# BOOST.net
KiCad netlist of a schematic drawn in Altium Designer
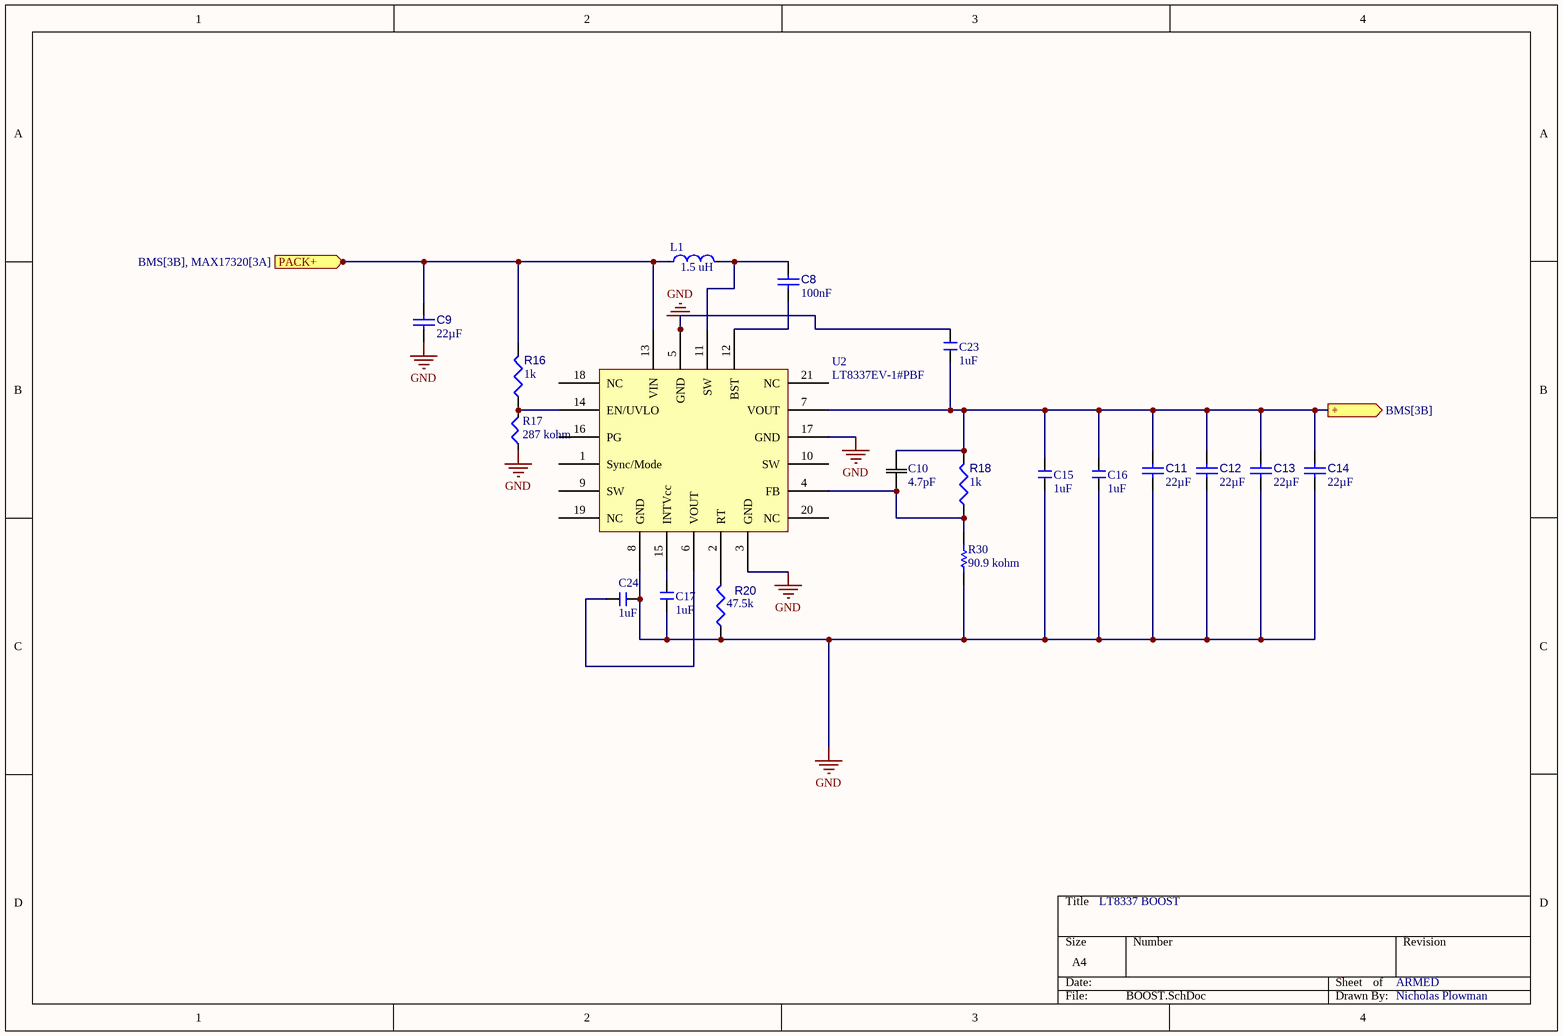
[diagram p0: BOOST.SchDoc]

(export (version "E")
  (design (tool "Eeschema 10.0.6"))
  (components
    (comp (ref "C8")
      (value "100nF")
      (footprint "CAPC1005X56X25LL10T15")
      (description "Chip Capacitor, 0.1 uF, +/- 5%, 16 V, 0402 (1005 Metric)")
      (fields (field (name "TOLERANCE") "5%") (field (name "Comment") "Capacitor 0.1 uF +/- 5% 16 V 0402"))
      (libsource (lib "Americas- Augmented Reality for Medicine- University of Calgary") (part "CAP-NP-2"))
    )
    (comp (ref "C9")
      (value "22µF")
      (footprint "CAPC0805(2012)145_L")
      (description "Chip Capacitor, 22µF +/-40%, 16V, 0805, Thickness 1.45 mm")
      (fields (field (name "TOLERANCE") "5%") (field (name "Comment") "Capacitor 22µF +/-40% 16V 0805"))
      (libsource (lib "Americas- Augmented Reality for Medicine- University of Calgary") (part "CAP-NP-2"))
    )
    (comp (ref "C10")
      (value "600L4R7BT200T4K")
      (footprint "600L4R7BT200T4K-Footprint-1")
      (description "Cap Cer 4.7PF 200V C0G/NP0 0402")
      (fields (field (name "PARAMETER 1") "4.7pF"))
      (libsource (lib "Americas- Augmented Reality for Medicine- University of Calgary") (part "600L4R7BT200T4K-Symbol-1"))
    )
    (comp (ref "C11")
      (value "22µF")
      (footprint "CAPC0805(2012)145_L")
      (description "Chip Capacitor, 22µF +/-40%, 16V, 0805, Thickness 1.45 mm")
      (fields (field (name "TOLERANCE") "5%") (field (name "Comment") "Capacitor 22µF +/-40% 16V 0805"))
      (libsource (lib "Americas- Augmented Reality for Medicine- University of Calgary") (part "CAP-NP-2"))
    )
    (comp (ref "C12")
      (value "22µF")
      (footprint "CAPC0805(2012)145_L")
      (description "Chip Capacitor, 22µF +/-40%, 16V, 0805, Thickness 1.45 mm")
      (fields (field (name "TOLERANCE") "5%") (field (name "Comment") "Capacitor 22µF +/-40% 16V 0805"))
      (libsource (lib "Americas- Augmented Reality for Medicine- University of Calgary") (part "CAP-NP-2"))
    )
    (comp (ref "C13")
      (value "22µF")
      (footprint "CAPC0805(2012)145_L")
      (description "Chip Capacitor, 22µF +/-40%, 16V, 0805, Thickness 1.45 mm")
      (fields (field (name "TOLERANCE") "5%") (field (name "Comment") "Capacitor 22µF +/-40% 16V 0805"))
      (libsource (lib "Americas- Augmented Reality for Medicine- University of Calgary") (part "CAP-NP-2"))
    )
    (comp (ref "C14")
      (value "22µF")
      (footprint "CAPC0805(2012)145_L")
      (description "Chip Capacitor, 22µF +/-40%, 16V, 0805, Thickness 1.45 mm")
      (fields (field (name "TOLERANCE") "5%") (field (name "Comment") "Capacitor 22µF +/-40% 16V 0805"))
      (libsource (lib "Americas- Augmented Reality for Medicine- University of Calgary") (part "CAP-NP-2"))
    )
    (comp (ref "C15")
      (value "25V 1uF 0603 CAP")
      (footprint "25V 1uF 0603 CAP-Footprint-1")
      (description "0603 1 uF 25 V ±10 % Tolerance X5R SMT Multilayer Ceramic Capacitor")
      (fields (field (name "PARAMETER 1") "1uF"))
      (libsource (lib "Americas- Augmented Reality for Medicine- University of Calgary") (part "1uF"))
    )
    (comp (ref "C16")
      (value "25V 1uF 0603 CAP")
      (footprint "25V 1uF 0603 CAP-Footprint-1")
      (description "0603 1 uF 25 V ±10 % Tolerance X5R SMT Multilayer Ceramic Capacitor")
      (fields (field (name "PARAMETER 1") "1uF"))
      (libsource (lib "Americas- Augmented Reality for Medicine- University of Calgary") (part "1uF"))
    )
    (comp (ref "C17")
      (value "25V 1uF 0603 CAP")
      (footprint "25V 1uF 0603 CAP-Footprint-1")
      (description "0603 1 uF 25 V ±10 % Tolerance X5R SMT Multilayer Ceramic Capacitor")
      (fields (field (name "PARAMETER 1") "1uF"))
      (libsource (lib "Americas- Augmented Reality for Medicine- University of Calgary") (part "1uF"))
    )
    (comp (ref "C23")
      (value "25V 1uF 0603 CAP")
      (footprint "25V 1uF 0603 CAP-Footprint-1")
      (description "0603 1 uF 25 V ±10 % Tolerance X5R SMT Multilayer Ceramic Capacitor")
      (fields (field (name "PARAMETER 1") "1uF"))
      (libsource (lib "Americas- Augmented Reality for Medicine- University of Calgary") (part "1uF"))
    )
    (comp (ref "C24")
      (value "25V 1uF 0603 CAP")
      (footprint "25V 1uF 0603 CAP-Footprint-1")
      (description "0603 1 uF 25 V ±10 % Tolerance X5R SMT Multilayer Ceramic Capacitor")
      (fields (field (name "PARAMETER 1") "1uF"))
      (libsource (lib "Americas- Augmented Reality for Medicine- University of Calgary") (part "1uF"))
    )
    (comp (ref "L1")
      (value "1.5 uH")
      (footprint "FP-LB3225-2_5-0_2-IPC_A")
      (fields (field (name "Comment") "LBC3225T1R5MR"))
      (libsource (lib "Americas- Augmented Reality for Medicine- University of Calgary") (part "725321dda6339637d4d059423bc1c3c"))
    )
    (comp (ref "R16")
      (value "1k")
      (footprint "RESC0805(2012)_L")
      (description "1K 0.125W 5% 0805 (2012 Metric)  SMD")
      (fields (field (name "TOLERANCE") "5%") (field (name "POWER") "125mW"))
      (libsource (lib "Americas- Augmented Reality for Medicine- University of Calgary") (part "1KR5J"))
    )
    (comp (ref "R17")
      (value "RMCF0603FT287K")
      (footprint "RMCF0603FT287K-Footprint-1")
      (description "Res Thick Film 0603 287K Ohm 1% 1/10W ±100ppm/°C Molded SMD SMD Paper T/R")
      (fields (field (name "PARAMETER 1") "287 kohm"))
      (libsource (lib "Americas- Augmented Reality for Medicine- University of Calgary") (part "287KOhm Resistor 0603"))
    )
    (comp (ref "R18")
      (value "1k")
      (footprint "RESC0805(2012)_L")
      (description "1K 0.125W 5% 0805 (2012 Metric)  SMD")
      (fields (field (name "TOLERANCE") "5%") (field (name "POWER") "125mW"))
      (libsource (lib "Americas- Augmented Reality for Medicine- University of Calgary") (part "1KR5J"))
    )
    (comp (ref "R20")
      (value "47.5k")
      (footprint "RESC0402(1005)_L")
      (description "47K5 0.063W 1% 0402 (1005 Metric)  SMD")
      (fields (field (name "TOLERANCE") "1%") (field (name "POWER") "63mW"))
      (libsource (lib "Americas- Augmented Reality for Medicine- University of Calgary") (part "47D5KR2F"))
    )
    (comp (ref "R30")
      (value "RC0402FR-0790K9L")
      (footprint "RESC1005X40X25ML05T10")
      (description "SMD Chip Resistor, 90.9 kOhm, ± 1%, 63 mW, 0402 [1005 Metric], Thick Film, General Purpose")
      (fields (field (name "PARAMETER 1") "90.9 kohm"))
      (libsource (lib "Americas- Augmented Reality for Medicine- University of Calgary") (part "RES"))
    )
    (comp (ref "U2")
      (value "LT8337EV-1#PBF")
      (footprint "LT8337EV-1#PBF-Footprint-1")
      (description "Conv DC-DC 2.7V to 28V Synchronous Step Up Single-Out 2.7V to 28V 5A 16-Pin LQFN EP Tray")
      (libsource (lib "Americas- Augmented Reality for Medicine- University of Calgary") (part "LT8337EV-1#PBF-Symbol-1"))
    )
  )
  (nets
    (net (code "1") (name "/+") (class "Default")
      (node (ref "C10") (pin "2") (pinfunction "2_2") (pintype "passive"))
      (node (ref "C11") (pin "2") (pinfunction "2_2") (pintype "passive"))
      (node (ref "C12") (pin "2") (pinfunction "2_2") (pintype "passive"))
      (node (ref "C13") (pin "2") (pinfunction "2_2") (pintype "passive"))
      (node (ref "C14") (pin "2") (pinfunction "2_2") (pintype "passive"))
      (node (ref "C15") (pin "2") (pinfunction "2_2") (pintype "passive"))
      (node (ref "C16") (pin "2") (pinfunction "2_2") (pintype "passive"))
      (node (ref "C23") (pin "2") (pinfunction "2_2") (pintype "passive"))
      (node (ref "R18") (pin "2") (pinfunction "2_2") (pintype "passive"))
      (node (ref "U2") (pin "7") (pinfunction "VOUT_7") (pintype "passive"))
    )
    (net (code "2") (name "/PACK+") (class "Default")
      (node (ref "C9") (pin "2") (pinfunction "2_2") (pintype "passive"))
      (node (ref "L1") (pin "1") (pinfunction "1_1") (pintype "passive"))
      (node (ref "R16") (pin "2") (pinfunction "2_2") (pintype "passive"))
      (node (ref "U2") (pin "13") (pinfunction "VIN_13") (pintype "passive"))
    )
    (net (code "3") (name "GND") (class "Default")
      (node (ref "C11") (pin "1") (pinfunction "1_1") (pintype "passive"))
      (node (ref "C12") (pin "1") (pinfunction "1_1") (pintype "passive"))
      (node (ref "C13") (pin "1") (pinfunction "1_1") (pintype "passive"))
      (node (ref "C14") (pin "1") (pinfunction "1_1") (pintype "passive"))
      (node (ref "C15") (pin "1") (pinfunction "1_1") (pintype "passive"))
      (node (ref "C16") (pin "1") (pinfunction "1_1") (pintype "passive"))
      (node (ref "C17") (pin "1") (pinfunction "1_1") (pintype "passive"))
      (node (ref "C23") (pin "1") (pinfunction "1_1") (pintype "passive"))
      (node (ref "C24") (pin "1") (pinfunction "1_1") (pintype "passive"))
      (node (ref "C9") (pin "1") (pinfunction "1_1") (pintype "passive"))
      (node (ref "R17") (pin "1") (pinfunction "1_1") (pintype "passive"))
      (node (ref "R20") (pin "1") (pinfunction "1_1") (pintype "passive"))
      (node (ref "R30") (pin "1") (pinfunction "1_1") (pintype "passive"))
      (node (ref "U2") (pin "17") (pinfunction "GND_17") (pintype "passive"))
      (node (ref "U2") (pin "3") (pinfunction "GND_3") (pintype "passive"))
      (node (ref "U2") (pin "5") (pinfunction "GND_5") (pintype "passive"))
      (node (ref "U2") (pin "8") (pinfunction "GND_8") (pintype "passive"))
    )
    (net (code "4") (name "Net-(C8-Pad2)") (class "Default")
      (node (ref "C8") (pin "2") (pinfunction "2_2") (pintype "passive"))
      (node (ref "L1") (pin "2") (pinfunction "2_2") (pintype "passive"))
      (node (ref "U2") (pin "11") (pinfunction "SW_11") (pintype "passive"))
    )
    (net (code "5") (name "Net-(C24-Pad2)") (class "Default")
      (node (ref "C24") (pin "2") (pinfunction "2_2") (pintype "passive"))
      (node (ref "U2") (pin "6") (pinfunction "VOUT_6") (pintype "passive"))
    )
    (net (code "6") (name "Net-(U2-BST)") (class "Default")
      (node (ref "C8") (pin "1") (pinfunction "1_1") (pintype "passive"))
      (node (ref "U2") (pin "12") (pinfunction "BST_12") (pintype "passive"))
    )
    (net (code "7") (name "Net-(U2-EN{slash}UVLO)") (class "Default")
      (node (ref "R16") (pin "1") (pinfunction "1_1") (pintype "passive"))
      (node (ref "R17") (pin "2") (pinfunction "2_2") (pintype "passive"))
      (node (ref "U2") (pin "14") (pinfunction "EN/UVLO_14") (pintype "passive"))
    )
    (net (code "8") (name "Net-(U2-FB)") (class "Default")
      (node (ref "C10") (pin "1") (pinfunction "1_1") (pintype "passive"))
      (node (ref "R18") (pin "1") (pinfunction "1_1") (pintype "passive"))
      (node (ref "R30") (pin "2") (pinfunction "2_2") (pintype "passive"))
      (node (ref "U2") (pin "4") (pinfunction "FB_4") (pintype "passive"))
    )
    (net (code "9") (name "Net-(U2-INTVcc)") (class "Default")
      (node (ref "C17") (pin "2") (pinfunction "2_2") (pintype "passive"))
      (node (ref "U2") (pin "15") (pinfunction "INTVcc_15") (pintype "passive"))
    )
    (net (code "10") (name "Net-(U2-RT)") (class "Default")
      (node (ref "R20") (pin "2") (pinfunction "2_2") (pintype "passive"))
      (node (ref "U2") (pin "2") (pinfunction "RT_2") (pintype "passive"))
    )
    (net (code "11") (name "unconnected-(U2-NC-Pad18)") (class "Default")
      (node (ref "U2") (pin "18") (pinfunction "NC_18") (pintype "passive"))
    )
    (net (code "12") (name "unconnected-(U2-NC-Pad19)") (class "Default")
      (node (ref "U2") (pin "19") (pinfunction "NC_19") (pintype "passive"))
    )
    (net (code "13") (name "unconnected-(U2-NC-Pad20)") (class "Default")
      (node (ref "U2") (pin "20") (pinfunction "NC_20") (pintype "passive"))
    )
    (net (code "14") (name "unconnected-(U2-NC-Pad21)") (class "Default")
      (node (ref "U2") (pin "21") (pinfunction "NC_21") (pintype "passive"))
    )
    (net (code "15") (name "unconnected-(U2-PG-Pad16)") (class "Default")
      (node (ref "U2") (pin "16") (pinfunction "PG_16") (pintype "passive"))
    )
    (net (code "16") (name "unconnected-(U2-SW-Pad9)") (class "Default")
      (node (ref "U2") (pin "9") (pinfunction "SW_9") (pintype "passive"))
    )
    (net (code "17") (name "unconnected-(U2-SW-Pad10)") (class "Default")
      (node (ref "U2") (pin "10") (pinfunction "SW_10") (pintype "passive"))
    )
    (net (code "18") (name "unconnected-(U2-Sync{slash}Mode-Pad1)") (class "Default")
      (node (ref "U2") (pin "1") (pinfunction "Sync/Mode_1") (pintype "passive"))
    )
  )
)
